# STSPIN32F0A_ESC5.net
KiCad netlist of a schematic drawn in Altium Designer
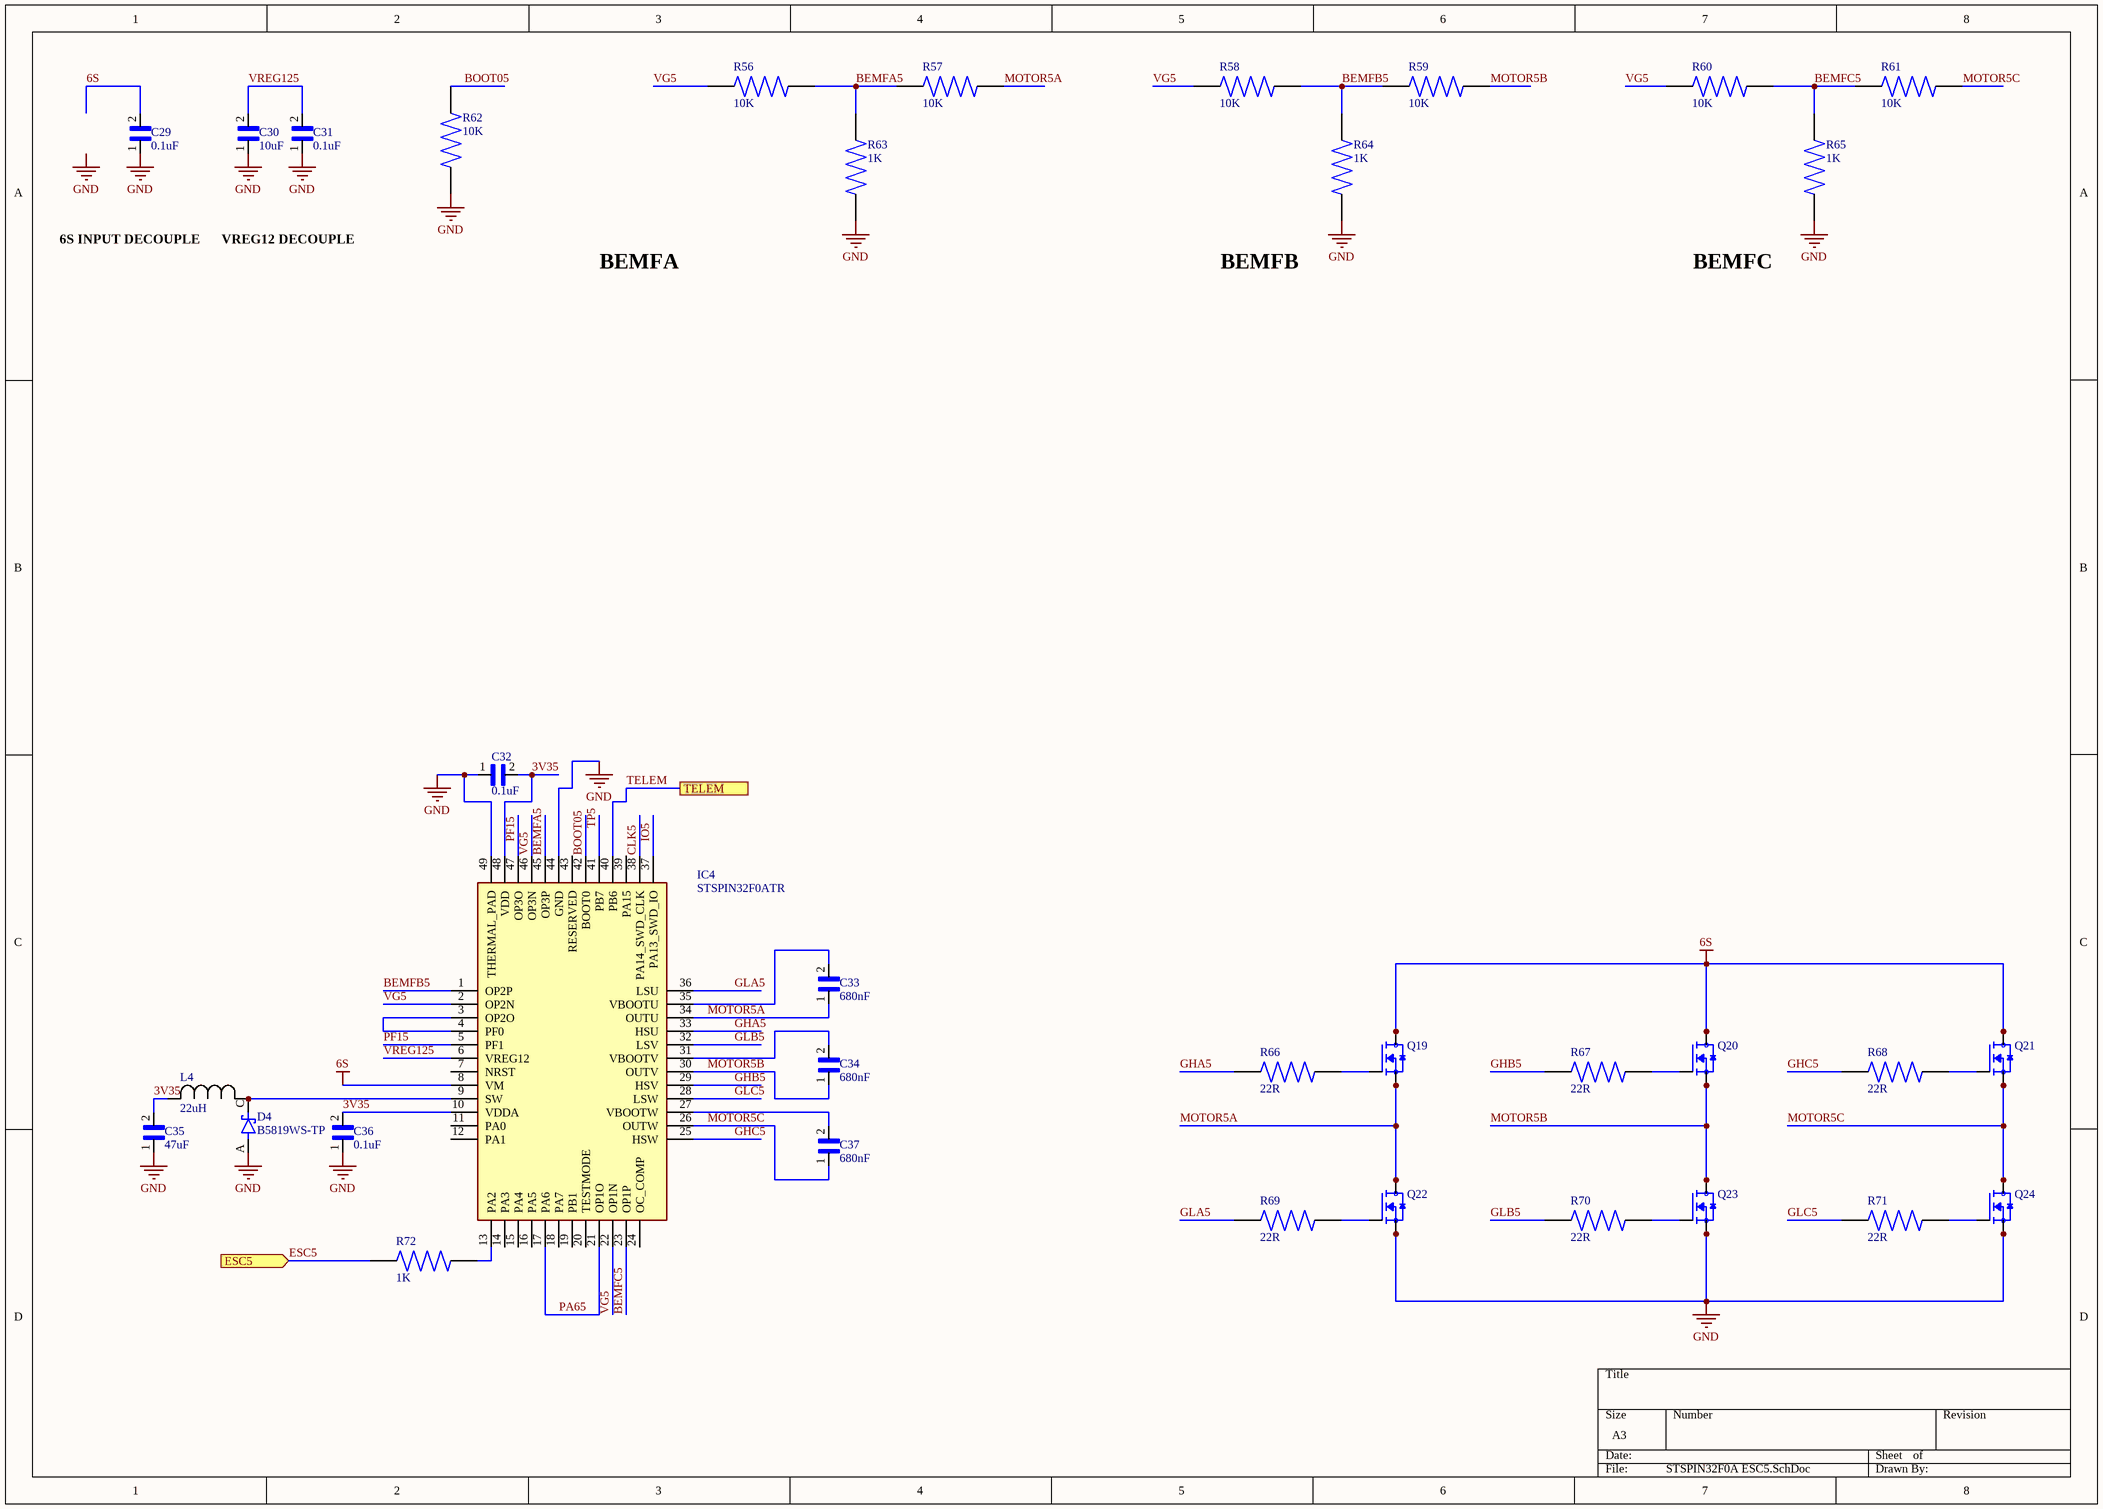
[diagram p0: STSPIN32F0A ESC5.SchDoc]

(export (version "E")
  (design (tool "Eeschema 10.0.6"))
  (components
    (comp (ref "C29")
      (value "0.1uF")
      (footprint "CAPC1005X55N")
      (fields (field (name "MP") "GRM1555C1H222JA01D"))
      (libsource (lib "GRM1555C1H222JA01D") (part "GRM1555C1H222JA01D"))
    )
    (comp (ref "C30")
      (value "10uF")
      (footprint "CAPC1608X90N")
      (description "SMD Capacitor X7R(EIA) with Capacitance: 0.22uF Tol. 5%. Rated Voltage: 25Vdc")
      (fields (field (name "MP") "GRM188R71E224JA88D"))
      (libsource (lib "GRM188R71E224JA88D") (part "GRM188R71E224JA88D"))
    )
    (comp (ref "C31")
      (value "0.1uF")
      (footprint "CAPC1005X55N")
      (fields (field (name "MP") "GRM1555C1H222JA01D"))
      (libsource (lib "GRM1555C1H222JA01D") (part "GRM1555C1H222JA01D"))
    )
    (comp (ref "C32")
      (value "0.1uF")
      (footprint "CAPC1005X55N")
      (fields (field (name "MP") "GRM1555C1H222JA01D"))
      (libsource (lib "") (part "GRM1555C1H222JA01D_1"))
    )
    (comp (ref "C33")
      (value "680nF")
      (footprint "CAPC1005X55N")
      (fields (field (name "MP") "GRM1555C1H222JA01D"))
      (libsource (lib "GRM1555C1H222JA01D") (part "GRM1555C1H222JA01D"))
    )
    (comp (ref "C34")
      (value "680nF")
      (footprint "CAPC1005X55N")
      (fields (field (name "MP") "GRM1555C1H222JA01D"))
      (libsource (lib "GRM1555C1H222JA01D") (part "GRM1555C1H222JA01D"))
    )
    (comp (ref "C35")
      (value "47uF")
      (footprint "CAPC1608X90N")
      (description "SMD Capacitor X7R(EIA) with Capacitance: 0.22uF Tol. 5%. Rated Voltage: 25Vdc")
      (fields (field (name "MP") "GRM188R71E224JA88D"))
      (libsource (lib "GRM188R71E224JA88D") (part "GRM188R71E224JA88D"))
    )
    (comp (ref "C36")
      (value "0.1uF")
      (footprint "CAPC1005X55N")
      (fields (field (name "MP") "GRM1555C1H222JA01D"))
      (libsource (lib "GRM1555C1H222JA01D") (part "GRM1555C1H222JA01D"))
    )
    (comp (ref "C37")
      (value "680nF")
      (footprint "CAPC1005X55N")
      (fields (field (name "MP") "GRM1555C1H222JA01D"))
      (libsource (lib "GRM1555C1H222JA01D") (part "GRM1555C1H222JA01D"))
    )
    (comp (ref "D4")
      (value "B5819WS-TP")
      (footprint "SOD2512X115N")
      (fields (field (name "MF") "{'manufacturer': u'Micro Commercial Components'}"))
      (libsource (lib "SnapEDA_Library") (part "B5819WS-TP"))
    )
    (comp (ref "IC4")
      (value "STSPIN32F0ATR")
      (footprint "SamacSys:QFN50P700X700X100-49N-D")
      (description "Integrated Circuit")
      (fields (field (name "MOUSER PART NUMBER") "511-STSPIN32F0ATR"))
      (libsource (lib "SamacSys") (part "STSPIN32F0ATR"))
    )
    (comp (ref "L4")
      (value "22uH")
      (footprint "IND_BOURNS_SRN3015")
      (description "No Description Available")
      (fields
        (field (name "MANUFACTURER_PART_NUMBER") "SRN3015-220M")
        (field (name "COPYRIGHT") "Copyright (C) 2022 Ultra Librarian. All rights reserved.")
      )
      (libsource (lib "SRN3015-220M") (part "SRN3015-220M"))
    )
    (comp (ref "Q19")
      (value "TPHR8504PL,L1Q")
      (footprint "TRANS_TPHR8504PL,L1Q")
      (description "N-Channel 40V 150A (Tc) 1W (Ta), 170W (Tc) Surface Mount 8-SOP Advance (5x5)")
      (fields (field (name "MF") "Toshiba Semiconductor"))
      (libsource (lib "TPHR8504PL_L1Q") (part "TPHR8504PL,L1Q"))
    )
    (comp (ref "Q20")
      (value "TPHR8504PL,L1Q")
      (footprint "TRANS_TPHR8504PL,L1Q")
      (description "N-Channel 40V 150A (Tc) 1W (Ta), 170W (Tc) Surface Mount 8-SOP Advance (5x5)")
      (fields (field (name "MF") "Toshiba Semiconductor"))
      (libsource (lib "TPHR8504PL_L1Q") (part "TPHR8504PL,L1Q"))
    )
    (comp (ref "Q21")
      (value "TPHR8504PL,L1Q")
      (footprint "TRANS_TPHR8504PL,L1Q")
      (description "N-Channel 40V 150A (Tc) 1W (Ta), 170W (Tc) Surface Mount 8-SOP Advance (5x5)")
      (fields (field (name "MF") "Toshiba Semiconductor"))
      (libsource (lib "TPHR8504PL_L1Q") (part "TPHR8504PL,L1Q"))
    )
    (comp (ref "Q22")
      (value "TPHR8504PL,L1Q")
      (footprint "TRANS_TPHR8504PL,L1Q")
      (description "N-Channel 40V 150A (Tc) 1W (Ta), 170W (Tc) Surface Mount 8-SOP Advance (5x5)")
      (fields (field (name "MF") "Toshiba Semiconductor"))
      (libsource (lib "TPHR8504PL_L1Q") (part "TPHR8504PL,L1Q"))
    )
    (comp (ref "Q23")
      (value "TPHR8504PL,L1Q")
      (footprint "TRANS_TPHR8504PL,L1Q")
      (description "N-Channel 40V 150A (Tc) 1W (Ta), 170W (Tc) Surface Mount 8-SOP Advance (5x5)")
      (fields (field (name "MF") "Toshiba Semiconductor"))
      (libsource (lib "TPHR8504PL_L1Q") (part "TPHR8504PL,L1Q"))
    )
    (comp (ref "Q24")
      (value "TPHR8504PL,L1Q")
      (footprint "TRANS_TPHR8504PL,L1Q")
      (description "N-Channel 40V 150A (Tc) 1W (Ta), 170W (Tc) Surface Mount 8-SOP Advance (5x5)")
      (fields (field (name "MF") "Toshiba Semiconductor"))
      (libsource (lib "TPHR8504PL_L1Q") (part "TPHR8504PL,L1Q"))
    )
    (comp (ref "R56")
      (value "10K")
      (footprint "RESC1005X37N")
      (fields (field (name "MP") "RE0402BRE07330KL") (field (name "MF") "{'manufacturer': u'Yageo'}"))
      (libsource (lib "SnapEDA_Library") (part "RE0402BRE07330KL"))
    )
    (comp (ref "R57")
      (value "10K")
      (footprint "RESC1005X37N")
      (fields (field (name "MP") "RE0402BRE07330KL") (field (name "MF") "{'manufacturer': u'Yageo'}"))
      (libsource (lib "SnapEDA_Library") (part "RE0402BRE07330KL"))
    )
    (comp (ref "R58")
      (value "10K")
      (footprint "RESC1005X37N")
      (fields (field (name "MP") "RE0402BRE07330KL") (field (name "MF") "{'manufacturer': u'Yageo'}"))
      (libsource (lib "SnapEDA_Library") (part "RE0402BRE07330KL"))
    )
    (comp (ref "R59")
      (value "10K")
      (footprint "RESC1005X37N")
      (fields (field (name "MP") "RE0402BRE07330KL") (field (name "MF") "{'manufacturer': u'Yageo'}"))
      (libsource (lib "SnapEDA_Library") (part "RE0402BRE07330KL"))
    )
    (comp (ref "R60")
      (value "10K")
      (footprint "RESC1005X37N")
      (fields (field (name "MP") "RE0402BRE07330KL") (field (name "MF") "{'manufacturer': u'Yageo'}"))
      (libsource (lib "SnapEDA_Library") (part "RE0402BRE07330KL"))
    )
    (comp (ref "R61")
      (value "10K")
      (footprint "RESC1005X37N")
      (fields (field (name "MP") "RE0402BRE07330KL") (field (name "MF") "{'manufacturer': u'Yageo'}"))
      (libsource (lib "SnapEDA_Library") (part "RE0402BRE07330KL"))
    )
    (comp (ref "R62")
      (value "10K")
      (footprint "RESC1005X37N")
      (fields (field (name "MP") "RE0402BRE07330KL") (field (name "MF") "{'manufacturer': u'Yageo'}"))
      (libsource (lib "SnapEDA_Library") (part "RE0402BRE07330KL"))
    )
    (comp (ref "R63")
      (value "1K")
      (footprint "RESC1005X37N")
      (fields (field (name "MP") "RE0402BRE07330KL") (field (name "MF") "{'manufacturer': u'Yageo'}"))
      (libsource (lib "SnapEDA_Library") (part "RE0402BRE07330KL"))
    )
    (comp (ref "R64")
      (value "1K")
      (footprint "RESC1005X37N")
      (fields (field (name "MP") "RE0402BRE07330KL") (field (name "MF") "{'manufacturer': u'Yageo'}"))
      (libsource (lib "SnapEDA_Library") (part "RE0402BRE07330KL"))
    )
    (comp (ref "R65")
      (value "1K")
      (footprint "RESC1005X37N")
      (fields (field (name "MP") "RE0402BRE07330KL") (field (name "MF") "{'manufacturer': u'Yageo'}"))
      (libsource (lib "SnapEDA_Library") (part "RE0402BRE07330KL"))
    )
    (comp (ref "R66")
      (value "22R")
      (footprint "RESC1005X37N")
      (fields (field (name "MP") "RE0402BRE07330KL") (field (name "MF") "{'manufacturer': u'Yageo'}"))
      (libsource (lib "SnapEDA_Library") (part "RE0402BRE07330KL"))
    )
    (comp (ref "R67")
      (value "22R")
      (footprint "RESC1005X37N")
      (fields (field (name "MP") "RE0402BRE07330KL") (field (name "MF") "{'manufacturer': u'Yageo'}"))
      (libsource (lib "SnapEDA_Library") (part "RE0402BRE07330KL"))
    )
    (comp (ref "R68")
      (value "22R")
      (footprint "RESC1005X37N")
      (fields (field (name "MP") "RE0402BRE07330KL") (field (name "MF") "{'manufacturer': u'Yageo'}"))
      (libsource (lib "SnapEDA_Library") (part "RE0402BRE07330KL"))
    )
    (comp (ref "R69")
      (value "22R")
      (footprint "RESC1005X37N")
      (fields (field (name "MP") "RE0402BRE07330KL") (field (name "MF") "{'manufacturer': u'Yageo'}"))
      (libsource (lib "SnapEDA_Library") (part "RE0402BRE07330KL"))
    )
    (comp (ref "R70")
      (value "22R")
      (footprint "RESC1005X37N")
      (fields (field (name "MP") "RE0402BRE07330KL") (field (name "MF") "{'manufacturer': u'Yageo'}"))
      (libsource (lib "SnapEDA_Library") (part "RE0402BRE07330KL"))
    )
    (comp (ref "R71")
      (value "22R")
      (footprint "RESC1005X37N")
      (fields (field (name "MP") "RE0402BRE07330KL") (field (name "MF") "{'manufacturer': u'Yageo'}"))
      (libsource (lib "SnapEDA_Library") (part "RE0402BRE07330KL"))
    )
    (comp (ref "R72")
      (value "1K")
      (footprint "RESC1005X37N")
      (fields (field (name "MP") "RE0402BRE07330KL") (field (name "MF") "{'manufacturer': u'Yageo'}"))
      (libsource (lib "SnapEDA_Library") (part "RE0402BRE07330KL"))
    )
  )
  (nets
    (net (code "1") (name "/3V35") (class "Default")
      (node (ref "C32") (pin "2") (pinfunction "2_2") (pintype "passive"))
      (node (ref "C35") (pin "2") (pinfunction "2_2") (pintype "passive"))
      (node (ref "C36") (pin "2") (pinfunction "2_2") (pintype "passive"))
      (node (ref "IC4") (pin "10") (pinfunction "VDDA_10") (pintype "passive"))
      (node (ref "IC4") (pin "48") (pinfunction "VDD_48") (pintype "passive"))
      (node (ref "L4") (pin "2") (pinfunction "2_2") (pintype "passive"))
    )
    (net (code "2") (name "/BEMFA5") (class "Default")
      (node (ref "IC4") (pin "45") (pinfunction "OP3P_45") (pintype "passive"))
      (node (ref "R56") (pin "1") (pinfunction "1_1") (pintype "passive"))
      (node (ref "R57") (pin "2") (pinfunction "2_2") (pintype "passive"))
      (node (ref "R63") (pin "1") (pinfunction "1_1") (pintype "passive"))
    )
    (net (code "3") (name "/BEMFB5") (class "Default")
      (node (ref "IC4") (pin "1") (pinfunction "OP2P_1") (pintype "passive"))
      (node (ref "R58") (pin "1") (pinfunction "1_1") (pintype "passive"))
      (node (ref "R59") (pin "2") (pinfunction "2_2") (pintype "passive"))
      (node (ref "R64") (pin "1") (pinfunction "1_1") (pintype "passive"))
    )
    (net (code "4") (name "/BEMFC5") (class "Default")
      (node (ref "IC4") (pin "23") (pinfunction "OP1P_23") (pintype "passive"))
      (node (ref "R60") (pin "1") (pinfunction "1_1") (pintype "passive"))
      (node (ref "R61") (pin "2") (pinfunction "2_2") (pintype "passive"))
      (node (ref "R65") (pin "1") (pinfunction "1_1") (pintype "passive"))
    )
    (net (code "5") (name "/BOOT05") (class "Default")
      (node (ref "IC4") (pin "42") (pinfunction "BOOT0_42") (pintype "passive"))
      (node (ref "R62") (pin "2") (pinfunction "2_2") (pintype "passive"))
    )
    (net (code "6") (name "/CLK5") (class "Default")
      (node (ref "IC4") (pin "38") (pinfunction "PA14_SWD_CLK_38") (pintype "passive"))
    )
    (net (code "7") (name "/ESC5") (class "Default")
      (node (ref "R72") (pin "1") (pinfunction "1_1") (pintype "passive"))
    )
    (net (code "8") (name "/GHA5") (class "Default")
      (node (ref "IC4") (pin "33") (pinfunction "HSU_33") (pintype "passive"))
      (node (ref "R66") (pin "2") (pinfunction "2_2") (pintype "passive"))
    )
    (net (code "9") (name "/GHB5") (class "Default")
      (node (ref "IC4") (pin "29") (pinfunction "HSV_29") (pintype "passive"))
      (node (ref "R67") (pin "2") (pinfunction "2_2") (pintype "passive"))
    )
    (net (code "10") (name "/GHC5") (class "Default")
      (node (ref "IC4") (pin "25") (pinfunction "HSW_25") (pintype "passive"))
      (node (ref "R68") (pin "2") (pinfunction "2_2") (pintype "passive"))
    )
    (net (code "11") (name "/GLA5") (class "Default")
      (node (ref "IC4") (pin "36") (pinfunction "LSU_36") (pintype "passive"))
      (node (ref "R69") (pin "2") (pinfunction "2_2") (pintype "passive"))
    )
    (net (code "12") (name "/GLB5") (class "Default")
      (node (ref "IC4") (pin "32") (pinfunction "LSV_32") (pintype "passive"))
      (node (ref "R70") (pin "2") (pinfunction "2_2") (pintype "passive"))
    )
    (net (code "13") (name "/GLC5") (class "Default")
      (node (ref "IC4") (pin "28") (pinfunction "LSW_28") (pintype "passive"))
      (node (ref "R71") (pin "2") (pinfunction "2_2") (pintype "passive"))
    )
    (net (code "14") (name "/IO5") (class "Default")
      (node (ref "IC4") (pin "37") (pinfunction "PA13_SWD_IO_37") (pintype "passive"))
    )
    (net (code "15") (name "/MOTOR5A") (class "Default")
      (node (ref "C33") (pin "1") (pinfunction "1_1") (pintype "passive"))
      (node (ref "IC4") (pin "34") (pinfunction "OUTU_34") (pintype "passive"))
      (node (ref "Q19") (pin "1") (pinfunction "S_1") (pintype "passive"))
      (node (ref "Q19") (pin "2") (pinfunction "S_2") (pintype "passive"))
      (node (ref "Q19") (pin "3") (pinfunction "S_3") (pintype "passive"))
      (node (ref "Q22") (pin "5") (pinfunction "D_5") (pintype "passive"))
      (node (ref "Q22") (pin "6") (pinfunction "D_6") (pintype "passive"))
      (node (ref "Q22") (pin "7") (pinfunction "D_7") (pintype "passive"))
      (node (ref "Q22") (pin "8") (pinfunction "D_8") (pintype "passive"))
      (node (ref "Q22") (pin "9") (pinfunction "D_9") (pintype "passive"))
      (node (ref "R57") (pin "1") (pinfunction "1_1") (pintype "passive"))
    )
    (net (code "16") (name "/MOTOR5B") (class "Default")
      (node (ref "C34") (pin "1") (pinfunction "1_1") (pintype "passive"))
      (node (ref "IC4") (pin "30") (pinfunction "OUTV_30") (pintype "passive"))
      (node (ref "Q20") (pin "1") (pinfunction "S_1") (pintype "passive"))
      (node (ref "Q20") (pin "2") (pinfunction "S_2") (pintype "passive"))
      (node (ref "Q20") (pin "3") (pinfunction "S_3") (pintype "passive"))
      (node (ref "Q23") (pin "5") (pinfunction "D_5") (pintype "passive"))
      (node (ref "Q23") (pin "6") (pinfunction "D_6") (pintype "passive"))
      (node (ref "Q23") (pin "7") (pinfunction "D_7") (pintype "passive"))
      (node (ref "Q23") (pin "8") (pinfunction "D_8") (pintype "passive"))
      (node (ref "Q23") (pin "9") (pinfunction "D_9") (pintype "passive"))
      (node (ref "R59") (pin "1") (pinfunction "1_1") (pintype "passive"))
    )
    (net (code "17") (name "/MOTOR5C") (class "Default")
      (node (ref "C37") (pin "1") (pinfunction "1_1") (pintype "passive"))
      (node (ref "IC4") (pin "26") (pinfunction "OUTW_26") (pintype "passive"))
      (node (ref "Q21") (pin "1") (pinfunction "S_1") (pintype "passive"))
      (node (ref "Q21") (pin "2") (pinfunction "S_2") (pintype "passive"))
      (node (ref "Q21") (pin "3") (pinfunction "S_3") (pintype "passive"))
      (node (ref "Q24") (pin "5") (pinfunction "D_5") (pintype "passive"))
      (node (ref "Q24") (pin "6") (pinfunction "D_6") (pintype "passive"))
      (node (ref "Q24") (pin "7") (pinfunction "D_7") (pintype "passive"))
      (node (ref "Q24") (pin "8") (pinfunction "D_8") (pintype "passive"))
      (node (ref "Q24") (pin "9") (pinfunction "D_9") (pintype "passive"))
      (node (ref "R61") (pin "1") (pinfunction "1_1") (pintype "passive"))
    )
    (net (code "18") (name "/PA65") (class "Default")
      (node (ref "IC4") (pin "17") (pinfunction "PA6_17") (pintype "passive"))
      (node (ref "IC4") (pin "21") (pinfunction "OP1O_21") (pintype "passive"))
    )
    (net (code "19") (name "/PF15") (class "Default")
      (node (ref "IC4") (pin "47") (pinfunction "OP3O_47") (pintype "passive"))
      (node (ref "IC4") (pin "5") (pinfunction "PF1_5") (pintype "passive"))
    )
    (net (code "20") (name "/TELEM") (class "Default")
      (node (ref "IC4") (pin "40") (pinfunction "PB6_40") (pintype "passive"))
    )
    (net (code "21") (name "/TP5") (class "Default")
      (node (ref "IC4") (pin "41") (pinfunction "PB7_41") (pintype "passive"))
    )
    (net (code "22") (name "/VG5") (class "Default")
      (node (ref "IC4") (pin "2") (pinfunction "OP2N_2") (pintype "passive"))
      (node (ref "IC4") (pin "22") (pinfunction "OP1N_22") (pintype "passive"))
      (node (ref "IC4") (pin "46") (pinfunction "OP3N_46") (pintype "passive"))
      (node (ref "R56") (pin "2") (pinfunction "2_2") (pintype "passive"))
      (node (ref "R58") (pin "2") (pinfunction "2_2") (pintype "passive"))
      (node (ref "R60") (pin "2") (pinfunction "2_2") (pintype "passive"))
    )
    (net (code "23") (name "/VREG125") (class "Default")
      (node (ref "C30") (pin "2") (pinfunction "2_2") (pintype "passive"))
      (node (ref "C31") (pin "2") (pinfunction "2_2") (pintype "passive"))
      (node (ref "IC4") (pin "6") (pinfunction "VREG12_6") (pintype "passive"))
    )
    (net (code "24") (name "6S") (class "Default")
      (node (ref "C29") (pin "2") (pinfunction "2_2") (pintype "passive"))
      (node (ref "IC4") (pin "8") (pinfunction "VM_8") (pintype "passive"))
      (node (ref "Q19") (pin "5") (pinfunction "D_5") (pintype "passive"))
      (node (ref "Q19") (pin "6") (pinfunction "D_6") (pintype "passive"))
      (node (ref "Q19") (pin "7") (pinfunction "D_7") (pintype "passive"))
      (node (ref "Q19") (pin "8") (pinfunction "D_8") (pintype "passive"))
      (node (ref "Q19") (pin "9") (pinfunction "D_9") (pintype "passive"))
      (node (ref "Q20") (pin "5") (pinfunction "D_5") (pintype "passive"))
      (node (ref "Q20") (pin "6") (pinfunction "D_6") (pintype "passive"))
      (node (ref "Q20") (pin "7") (pinfunction "D_7") (pintype "passive"))
      (node (ref "Q20") (pin "8") (pinfunction "D_8") (pintype "passive"))
      (node (ref "Q20") (pin "9") (pinfunction "D_9") (pintype "passive"))
      (node (ref "Q21") (pin "5") (pinfunction "D_5") (pintype "passive"))
      (node (ref "Q21") (pin "6") (pinfunction "D_6") (pintype "passive"))
      (node (ref "Q21") (pin "7") (pinfunction "D_7") (pintype "passive"))
      (node (ref "Q21") (pin "8") (pinfunction "D_8") (pintype "passive"))
      (node (ref "Q21") (pin "9") (pinfunction "D_9") (pintype "passive"))
    )
    (net (code "25") (name "GND") (class "Default")
      (node (ref "C29") (pin "1") (pinfunction "1_1") (pintype "passive"))
      (node (ref "C30") (pin "1") (pinfunction "1_1") (pintype "passive"))
      (node (ref "C31") (pin "1") (pinfunction "1_1") (pintype "passive"))
      (node (ref "C32") (pin "1") (pinfunction "1_1") (pintype "passive"))
      (node (ref "C35") (pin "1") (pinfunction "1_1") (pintype "passive"))
      (node (ref "C36") (pin "1") (pinfunction "1_1") (pintype "passive"))
      (node (ref "D4") (pin "A") (pinfunction "A_A") (pintype "passive"))
      (node (ref "IC4") (pin "44") (pinfunction "GND_44") (pintype "passive"))
      (node (ref "IC4") (pin "49") (pinfunction "THERMAL_PAD_49") (pintype "passive"))
      (node (ref "Q22") (pin "1") (pinfunction "S_1") (pintype "passive"))
      (node (ref "Q22") (pin "2") (pinfunction "S_2") (pintype "passive"))
      (node (ref "Q22") (pin "3") (pinfunction "S_3") (pintype "passive"))
      (node (ref "Q23") (pin "1") (pinfunction "S_1") (pintype "passive"))
      (node (ref "Q23") (pin "2") (pinfunction "S_2") (pintype "passive"))
      (node (ref "Q23") (pin "3") (pinfunction "S_3") (pintype "passive"))
      (node (ref "Q24") (pin "1") (pinfunction "S_1") (pintype "passive"))
      (node (ref "Q24") (pin "2") (pinfunction "S_2") (pintype "passive"))
      (node (ref "Q24") (pin "3") (pinfunction "S_3") (pintype "passive"))
      (node (ref "R62") (pin "1") (pinfunction "1_1") (pintype "passive"))
      (node (ref "R63") (pin "2") (pinfunction "2_2") (pintype "passive"))
      (node (ref "R64") (pin "2") (pinfunction "2_2") (pintype "passive"))
      (node (ref "R65") (pin "2") (pinfunction "2_2") (pintype "passive"))
    )
    (net (code "26") (name "Net-(D4-K)") (class "Default")
      (node (ref "D4") (pin "C") (pinfunction "K_C") (pintype "passive"))
      (node (ref "IC4") (pin "9") (pinfunction "SW_9") (pintype "passive"))
      (node (ref "L4") (pin "1") (pinfunction "1_1") (pintype "passive"))
    )
    (net (code "27") (name "Net-(IC4-OP2O)") (class "Default")
      (node (ref "IC4") (pin "3") (pinfunction "OP2O_3") (pintype "passive"))
      (node (ref "IC4") (pin "4") (pinfunction "PF0_4") (pintype "passive"))
    )
    (net (code "28") (name "Net-(IC4-PA2)") (class "Default")
      (node (ref "IC4") (pin "13") (pinfunction "PA2_13") (pintype "passive"))
      (node (ref "R72") (pin "2") (pinfunction "2_2") (pintype "passive"))
    )
    (net (code "29") (name "Net-(IC4-VBOOTU)") (class "Default")
      (node (ref "C33") (pin "2") (pinfunction "2_2") (pintype "passive"))
      (node (ref "IC4") (pin "35") (pinfunction "VBOOTU_35") (pintype "passive"))
    )
    (net (code "30") (name "Net-(IC4-VBOOTV)") (class "Default")
      (node (ref "C34") (pin "2") (pinfunction "2_2") (pintype "passive"))
      (node (ref "IC4") (pin "31") (pinfunction "VBOOTV_31") (pintype "passive"))
    )
    (net (code "31") (name "Net-(IC4-VBOOTW)") (class "Default")
      (node (ref "C37") (pin "2") (pinfunction "2_2") (pintype "passive"))
      (node (ref "IC4") (pin "27") (pinfunction "VBOOTW_27") (pintype "passive"))
    )
    (net (code "32") (name "Net-(Q19-G)") (class "Default")
      (node (ref "Q19") (pin "4") (pinfunction "G_4") (pintype "passive"))
      (node (ref "R66") (pin "1") (pinfunction "1_1") (pintype "passive"))
    )
    (net (code "33") (name "Net-(Q20-G)") (class "Default")
      (node (ref "Q20") (pin "4") (pinfunction "G_4") (pintype "passive"))
      (node (ref "R67") (pin "1") (pinfunction "1_1") (pintype "passive"))
    )
    (net (code "34") (name "Net-(Q21-G)") (class "Default")
      (node (ref "Q21") (pin "4") (pinfunction "G_4") (pintype "passive"))
      (node (ref "R68") (pin "1") (pinfunction "1_1") (pintype "passive"))
    )
    (net (code "35") (name "Net-(Q22-G)") (class "Default")
      (node (ref "Q22") (pin "4") (pinfunction "G_4") (pintype "passive"))
      (node (ref "R69") (pin "1") (pinfunction "1_1") (pintype "passive"))
    )
    (net (code "36") (name "Net-(Q23-G)") (class "Default")
      (node (ref "Q23") (pin "4") (pinfunction "G_4") (pintype "passive"))
      (node (ref "R70") (pin "1") (pinfunction "1_1") (pintype "passive"))
    )
    (net (code "37") (name "Net-(Q24-G)") (class "Default")
      (node (ref "Q24") (pin "4") (pinfunction "G_4") (pintype "passive"))
      (node (ref "R71") (pin "1") (pinfunction "1_1") (pintype "passive"))
    )
    (net (code "38") (name "unconnected-(IC4-NRST-Pad7)") (class "Default")
      (node (ref "IC4") (pin "7") (pinfunction "NRST_7") (pintype "passive"))
    )
    (net (code "39") (name "unconnected-(IC4-OC_COMP-Pad24)") (class "Default")
      (node (ref "IC4") (pin "24") (pinfunction "OC_COMP_24") (pintype "passive"))
    )
    (net (code "40") (name "unconnected-(IC4-PA0-Pad11)") (class "Default")
      (node (ref "IC4") (pin "11") (pinfunction "PA0_11") (pintype "passive"))
    )
    (net (code "41") (name "unconnected-(IC4-PA1-Pad12)") (class "Default")
      (node (ref "IC4") (pin "12") (pinfunction "PA1_12") (pintype "passive"))
    )
    (net (code "42") (name "unconnected-(IC4-PA3-Pad14)") (class "Default")
      (node (ref "IC4") (pin "14") (pinfunction "PA3_14") (pintype "passive"))
    )
    (net (code "43") (name "unconnected-(IC4-PA4-Pad15)") (class "Default")
      (node (ref "IC4") (pin "15") (pinfunction "PA4_15") (pintype "passive"))
    )
    (net (code "44") (name "unconnected-(IC4-PA5-Pad16)") (class "Default")
      (node (ref "IC4") (pin "16") (pinfunction "PA5_16") (pintype "passive"))
    )
    (net (code "45") (name "unconnected-(IC4-PA7-Pad18)") (class "Default")
      (node (ref "IC4") (pin "18") (pinfunction "PA7_18") (pintype "passive"))
    )
    (net (code "46") (name "unconnected-(IC4-PA15-Pad39)") (class "Default")
      (node (ref "IC4") (pin "39") (pinfunction "PA15_39") (pintype "passive"))
    )
    (net (code "47") (name "unconnected-(IC4-PB1-Pad19)") (class "Default")
      (node (ref "IC4") (pin "19") (pinfunction "PB1_19") (pintype "passive"))
    )
    (net (code "48") (name "unconnected-(IC4-RESERVED-Pad43)") (class "Default")
      (node (ref "IC4") (pin "43") (pinfunction "RESERVED_43") (pintype "passive"))
    )
    (net (code "49") (name "unconnected-(IC4-TESTMODE-Pad20)") (class "Default")
      (node (ref "IC4") (pin "20") (pinfunction "TESTMODE_20") (pintype "passive"))
    )
  )
)
